# User_-_LED_Indicators.net
KiCad netlist of a schematic drawn in Altium Designer
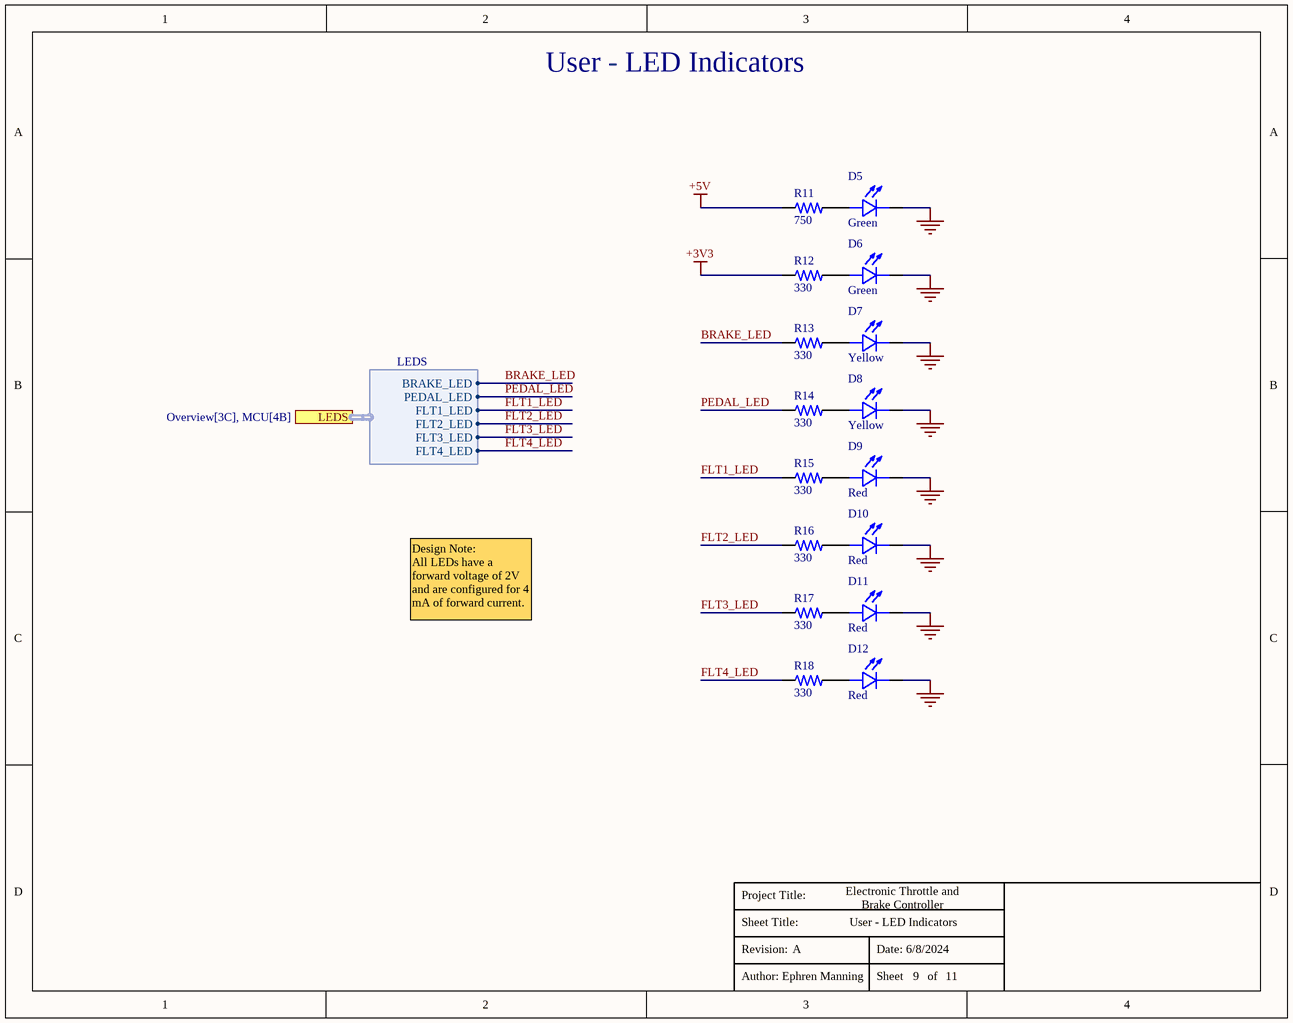
[diagram p0: User - LED Indicators.SchDoc]

(export (version "E")
  (design (tool "Eeschema 10.0.6"))
  (components
    (comp (ref "D5")
      (value "Green")
      (footprint "Wurth-LED-0603-Footprint")
      (description "LED GREEN CLEAR 0603 2V Forward Voltage")
      (fields (field (name "DIGIKEY PART NUMBER") "732-4980-1-ND"))
      (libsource (lib "SAE @ UIC Formula Electric") (part "LED-Symbol 1"))
    )
    (comp (ref "D6")
      (value "Green")
      (footprint "Wurth-LED-0603-Footprint")
      (description "LED GREEN CLEAR 0603 2V Forward Voltage")
      (fields (field (name "DIGIKEY PART NUMBER") "732-4980-1-ND"))
      (libsource (lib "SAE @ UIC Formula Electric") (part "LED-Symbol 1"))
    )
    (comp (ref "D7")
      (value "Yellow")
      (footprint "Wurth-LED-0603-Footprint")
      (description "LED YELLOW CLEAR 0603 2V Forward Voltage")
      (fields (field (name "DIGIKEY PART NUMBER") "732-4981-1-ND"))
      (libsource (lib "SAE @ UIC Formula Electric") (part "LED-Symbol 1"))
    )
    (comp (ref "D8")
      (value "Yellow")
      (footprint "Wurth-LED-0603-Footprint")
      (description "LED YELLOW CLEAR 0603 2V Forward Voltage")
      (fields (field (name "DIGIKEY PART NUMBER") "732-4981-1-ND"))
      (libsource (lib "SAE @ UIC Formula Electric") (part "LED-Symbol 1"))
    )
    (comp (ref "D9")
      (value "Red")
      (footprint "LED_150060RS75000")
      (description "CLEAR RED LEAD 0603 2V Forward Voltage")
      (fields (field (name "DIGIKEY PART NUMBER") "732-4978-1-ND"))
      (libsource (lib "SAE @ UIC Formula Electric") (part "150060RS75000"))
    )
    (comp (ref "D10")
      (value "Red")
      (footprint "LED_150060RS75000")
      (description "CLEAR RED LEAD 0603 2V Forward Voltage")
      (fields (field (name "DIGIKEY PART NUMBER") "732-4978-1-ND"))
      (libsource (lib "SAE @ UIC Formula Electric") (part "150060RS75000"))
    )
    (comp (ref "D11")
      (value "Red")
      (footprint "LED_150060RS75000")
      (description "CLEAR RED LEAD 0603 2V Forward Voltage")
      (fields (field (name "DIGIKEY PART NUMBER") "732-4978-1-ND"))
      (libsource (lib "SAE @ UIC Formula Electric") (part "150060RS75000"))
    )
    (comp (ref "D12")
      (value "Red")
      (footprint "LED_150060RS75000")
      (description "CLEAR RED LEAD 0603 2V Forward Voltage")
      (fields (field (name "DIGIKEY PART NUMBER") "732-4978-1-ND"))
      (libsource (lib "SAE @ UIC Formula Electric") (part "150060RS75000"))
    )
    (comp (ref "R11")
      (value "750")
      (footprint "RES_0402-Footprint-1")
      (description "750 1% 1/16W 0402 Thick Film")
      (fields (field (name "DIGIKEY PART NUMBER") "311-750LRCT-ND"))
      (libsource (lib "SAE @ UIC Formula Electric") (part "RES_0402_Symbol"))
    )
    (comp (ref "R12")
      (value "330")
      (footprint "RES_0402-Footprint-1")
      (description "330 1% 1/16W 0402 Thick Film")
      (fields (field (name "DIGIKEY PART NUMBER") "311-330LRCT-ND"))
      (libsource (lib "SAE @ UIC Formula Electric") (part "RES_0402_Symbol"))
    )
    (comp (ref "R13")
      (value "330")
      (footprint "RES_0402-Footprint-1")
      (description "330 1% 1/16W 0402 Thick Film")
      (fields (field (name "DIGIKEY PART NUMBER") "311-330LRCT-ND"))
      (libsource (lib "SAE @ UIC Formula Electric") (part "RES_0402_Symbol"))
    )
    (comp (ref "R14")
      (value "330")
      (footprint "RES_0402-Footprint-1")
      (description "330 1% 1/16W 0402 Thick Film")
      (fields (field (name "DIGIKEY PART NUMBER") "311-330LRCT-ND"))
      (libsource (lib "SAE @ UIC Formula Electric") (part "RES_0402_Symbol"))
    )
    (comp (ref "R15")
      (value "330")
      (footprint "RES_0402-Footprint-1")
      (description "330 1% 1/16W 0402 Thick Film")
      (fields (field (name "DIGIKEY PART NUMBER") "311-330LRCT-ND"))
      (libsource (lib "SAE @ UIC Formula Electric") (part "RES_0402_Symbol"))
    )
    (comp (ref "R16")
      (value "330")
      (footprint "RES_0402-Footprint-1")
      (description "330 1% 1/16W 0402 Thick Film")
      (fields (field (name "DIGIKEY PART NUMBER") "311-330LRCT-ND"))
      (libsource (lib "SAE @ UIC Formula Electric") (part "RES_0402_Symbol"))
    )
    (comp (ref "R17")
      (value "330")
      (footprint "RES_0402-Footprint-1")
      (description "330 1% 1/16W 0402 Thick Film")
      (fields (field (name "DIGIKEY PART NUMBER") "311-330LRCT-ND"))
      (libsource (lib "SAE @ UIC Formula Electric") (part "RES_0402_Symbol"))
    )
    (comp (ref "R18")
      (value "330")
      (footprint "RES_0402-Footprint-1")
      (description "330 1% 1/16W 0402 Thick Film")
      (fields (field (name "DIGIKEY PART NUMBER") "311-330LRCT-ND"))
      (libsource (lib "SAE @ UIC Formula Electric") (part "RES_0402_Symbol"))
    )
  )
  (nets
    (net (code "2") (name "+3V3") (class "Default")
      (node (ref "R12") (pin "1") (pinfunction "1_1") (pintype "passive"))
    )
    (net (code "3") (name "+5V") (class "Default")
      (node (ref "R11") (pin "1") (pinfunction "1_1") (pintype "passive"))
    )
    (net (code "4") (name "/BRAKE_LED") (class "Default")
      (node (ref "R13") (pin "1") (pinfunction "1_1") (pintype "passive"))
    )
    (net (code "5") (name "/FLT1_LED") (class "Default")
      (node (ref "R15") (pin "1") (pinfunction "1_1") (pintype "passive"))
    )
    (net (code "6") (name "/FLT2_LED") (class "Default")
      (node (ref "R16") (pin "1") (pinfunction "1_1") (pintype "passive"))
    )
    (net (code "7") (name "/FLT3_LED") (class "Default")
      (node (ref "R17") (pin "1") (pinfunction "1_1") (pintype "passive"))
    )
    (net (code "8") (name "/FLT4_LED") (class "Default")
      (node (ref "R18") (pin "1") (pinfunction "1_1") (pintype "passive"))
    )
    (net (code "9") (name "/PEDAL_LED") (class "Default")
      (node (ref "R14") (pin "1") (pinfunction "1_1") (pintype "passive"))
    )
    (net (code "11") (name "GND") (class "Default")
      (node (ref "D10") (pin "C") (pinfunction "C_C") (pintype "passive"))
      (node (ref "D11") (pin "C") (pinfunction "C_C") (pintype "passive"))
      (node (ref "D12") (pin "C") (pinfunction "C_C") (pintype "passive"))
      (node (ref "D5") (pin "C") (pinfunction "C_C") (pintype "passive"))
      (node (ref "D6") (pin "C") (pinfunction "C_C") (pintype "passive"))
      (node (ref "D7") (pin "C") (pinfunction "C_C") (pintype "passive"))
      (node (ref "D8") (pin "C") (pinfunction "C_C") (pintype "passive"))
      (node (ref "D9") (pin "C") (pinfunction "C_C") (pintype "passive"))
    )
    (net (code "12") (name "Net-(D5-PadA)") (class "Default")
      (node (ref "D5") (pin "A") (pinfunction "A_A") (pintype "passive"))
      (node (ref "R11") (pin "2") (pinfunction "2_2") (pintype "passive"))
    )
    (net (code "13") (name "Net-(D6-PadA)") (class "Default")
      (node (ref "D6") (pin "A") (pinfunction "A_A") (pintype "passive"))
      (node (ref "R12") (pin "2") (pinfunction "2_2") (pintype "passive"))
    )
    (net (code "14") (name "Net-(D7-PadA)") (class "Default")
      (node (ref "D7") (pin "A") (pinfunction "A_A") (pintype "passive"))
      (node (ref "R13") (pin "2") (pinfunction "2_2") (pintype "passive"))
    )
    (net (code "15") (name "Net-(D8-PadA)") (class "Default")
      (node (ref "D8") (pin "A") (pinfunction "A_A") (pintype "passive"))
      (node (ref "R14") (pin "2") (pinfunction "2_2") (pintype "passive"))
    )
    (net (code "16") (name "Net-(D9-PadA)") (class "Default")
      (node (ref "D9") (pin "A") (pinfunction "A_A") (pintype "passive"))
      (node (ref "R15") (pin "2") (pinfunction "2_2") (pintype "passive"))
    )
    (net (code "17") (name "Net-(D10-PadA)") (class "Default")
      (node (ref "D10") (pin "A") (pinfunction "A_A") (pintype "passive"))
      (node (ref "R16") (pin "2") (pinfunction "2_2") (pintype "passive"))
    )
    (net (code "18") (name "Net-(D11-PadA)") (class "Default")
      (node (ref "D11") (pin "A") (pinfunction "A_A") (pintype "passive"))
      (node (ref "R17") (pin "2") (pinfunction "2_2") (pintype "passive"))
    )
    (net (code "19") (name "Net-(D12-PadA)") (class "Default")
      (node (ref "D12") (pin "A") (pinfunction "A_A") (pintype "passive"))
      (node (ref "R18") (pin "2") (pinfunction "2_2") (pintype "passive"))
    )
  )
)
